# cyclone4.net
KiCad netlist of a schematic drawn in Altium Designer
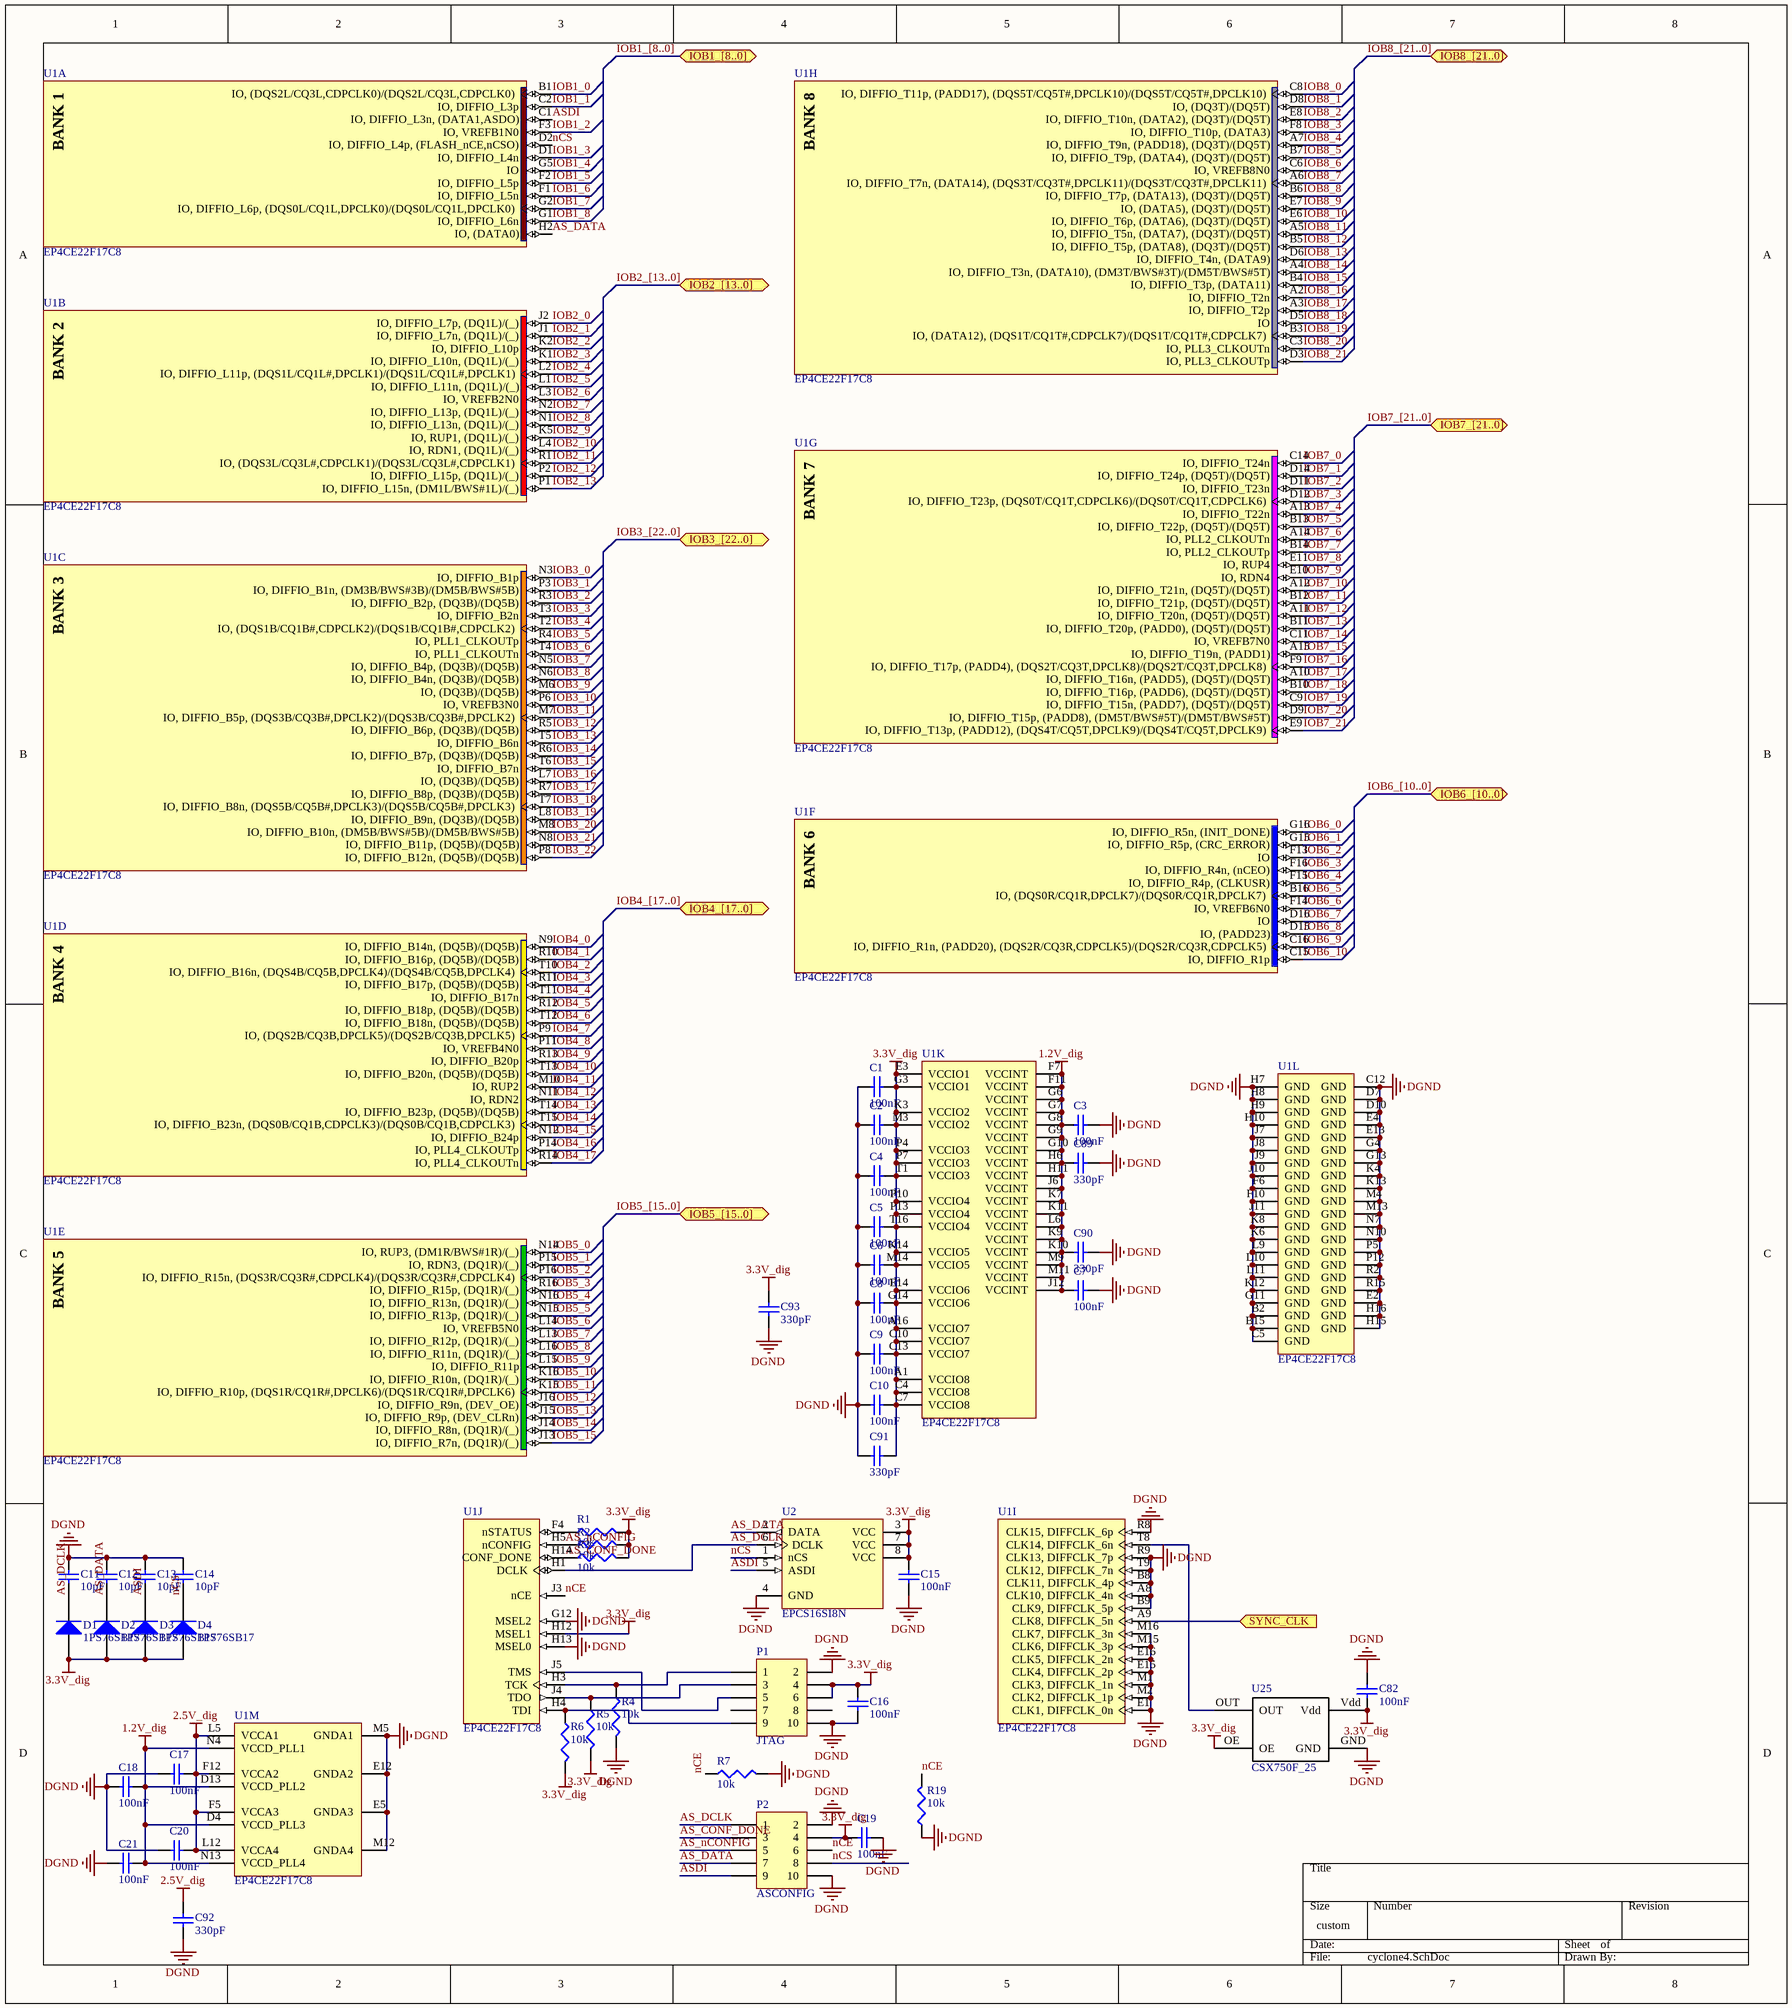
[diagram p0: cyclone4.SchDoc]

(export (version "E")
  (design (tool "Eeschema 10.0.6"))
  (components
    (comp (ref "C1")
      (value "100nF")
      (footprint "CAPC2012L")
      (description "Capacitor (Semiconductor SIM Model)")
      (fields (field (name "Comment") "Cap Semi"))
      (libsource (lib "Miscellaneous Devices") (part "Cap Semi"))
    )
    (comp (ref "C2")
      (value "100nF")
      (footprint "CAPC2012L")
      (description "Capacitor (Semiconductor SIM Model)")
      (fields (field (name "Comment") "Cap Semi"))
      (libsource (lib "Miscellaneous Devices") (part "Cap Semi"))
    )
    (comp (ref "C3")
      (value "100nF")
      (footprint "CAPC2012L")
      (description "Capacitor (Semiconductor SIM Model)")
      (fields (field (name "Comment") "Cap Semi"))
      (libsource (lib "Miscellaneous Devices") (part "Cap Semi"))
    )
    (comp (ref "C4")
      (value "100nF")
      (footprint "CAPC2012L")
      (description "Capacitor (Semiconductor SIM Model)")
      (fields (field (name "Comment") "Cap Semi"))
      (libsource (lib "Miscellaneous Devices") (part "Cap Semi"))
    )
    (comp (ref "C5")
      (value "100nF")
      (footprint "CAPC2012L")
      (description "Capacitor (Semiconductor SIM Model)")
      (fields (field (name "Comment") "Cap Semi"))
      (libsource (lib "Miscellaneous Devices") (part "Cap Semi"))
    )
    (comp (ref "C6")
      (value "100nF")
      (footprint "CAPC2012L")
      (description "Capacitor (Semiconductor SIM Model)")
      (fields (field (name "Comment") "Cap Semi"))
      (libsource (lib "Miscellaneous Devices") (part "Cap Semi"))
    )
    (comp (ref "C7")
      (value "100nF")
      (footprint "CAPC2012L")
      (description "Capacitor (Semiconductor SIM Model)")
      (fields (field (name "Comment") "Cap Semi"))
      (libsource (lib "Miscellaneous Devices") (part "Cap Semi"))
    )
    (comp (ref "C8")
      (value "100nF")
      (footprint "CAPC2012L")
      (description "Capacitor (Semiconductor SIM Model)")
      (fields (field (name "Comment") "Cap Semi"))
      (libsource (lib "Miscellaneous Devices") (part "Cap Semi"))
    )
    (comp (ref "C9")
      (value "100nF")
      (footprint "CAPC2012L")
      (description "Capacitor (Semiconductor SIM Model)")
      (fields (field (name "Comment") "Cap Semi"))
      (libsource (lib "Miscellaneous Devices") (part "Cap Semi"))
    )
    (comp (ref "C10")
      (value "100nF")
      (footprint "CAPC2012L")
      (description "Capacitor (Semiconductor SIM Model)")
      (fields (field (name "Comment") "Cap Semi"))
      (libsource (lib "Miscellaneous Devices") (part "Cap Semi"))
    )
    (comp (ref "C11")
      (value "10pF")
      (footprint "CAPC2012L")
      (description "Capacitor (Semiconductor SIM Model)")
      (fields (field (name "Comment") "Cap Semi"))
      (libsource (lib "Miscellaneous Devices") (part "Cap Semi"))
    )
    (comp (ref "C12")
      (value "10pF")
      (footprint "CAPC2012L")
      (description "Capacitor (Semiconductor SIM Model)")
      (fields (field (name "Comment") "Cap Semi"))
      (libsource (lib "Miscellaneous Devices") (part "Cap Semi"))
    )
    (comp (ref "C13")
      (value "10pF")
      (footprint "CAPC2012L")
      (description "Capacitor (Semiconductor SIM Model)")
      (fields (field (name "Comment") "Cap Semi"))
      (libsource (lib "Miscellaneous Devices") (part "Cap Semi"))
    )
    (comp (ref "C14")
      (value "10pF")
      (footprint "CAPC2012L")
      (description "Capacitor (Semiconductor SIM Model)")
      (fields (field (name "Comment") "Cap Semi"))
      (libsource (lib "Miscellaneous Devices") (part "Cap Semi"))
    )
    (comp (ref "C15")
      (value "100nF")
      (footprint "CAPC2012L")
      (description "Capacitor (Semiconductor SIM Model)")
      (fields (field (name "Comment") "Cap Semi"))
      (libsource (lib "Miscellaneous Devices") (part "Cap Semi"))
    )
    (comp (ref "C16")
      (value "100nF")
      (footprint "CAPC2012L")
      (description "Capacitor (Semiconductor SIM Model)")
      (fields (field (name "Comment") "Cap Semi"))
      (libsource (lib "Miscellaneous Devices") (part "Cap Semi"))
    )
    (comp (ref "C17")
      (value "100nF")
      (footprint "CAPC2012L")
      (description "Capacitor (Semiconductor SIM Model)")
      (fields (field (name "Comment") "Cap Semi"))
      (libsource (lib "Miscellaneous Devices") (part "Cap Semi"))
    )
    (comp (ref "C18")
      (value "100nF")
      (footprint "CAPC2012L")
      (description "Capacitor (Semiconductor SIM Model)")
      (fields (field (name "Comment") "Cap Semi"))
      (libsource (lib "Miscellaneous Devices") (part "Cap Semi"))
    )
    (comp (ref "C19")
      (value "100nF")
      (footprint "CAPC2012L")
      (description "Capacitor (Semiconductor SIM Model)")
      (fields (field (name "Comment") "Cap Semi"))
      (libsource (lib "Miscellaneous Devices") (part "Cap Semi"))
    )
    (comp (ref "C20")
      (value "100nF")
      (footprint "CAPC2012L")
      (description "Capacitor (Semiconductor SIM Model)")
      (fields (field (name "Comment") "Cap Semi"))
      (libsource (lib "Miscellaneous Devices") (part "Cap Semi"))
    )
    (comp (ref "C21")
      (value "100nF")
      (footprint "CAPC2012L")
      (description "Capacitor (Semiconductor SIM Model)")
      (fields (field (name "Comment") "Cap Semi"))
      (libsource (lib "Miscellaneous Devices") (part "Cap Semi"))
    )
    (comp (ref "C82")
      (value "100nF")
      (footprint "CAPC2012L")
      (description "Capacitor (Semiconductor SIM Model)")
      (fields (field (name "Comment") "Cap Semi"))
      (libsource (lib "Miscellaneous Devices") (part "Cap Semi"))
    )
    (comp (ref "C89")
      (value "330pF")
      (footprint "CAPC2012L")
      (description "Capacitor (Semiconductor SIM Model)")
      (fields (field (name "Comment") "Cap Semi"))
      (libsource (lib "Miscellaneous Devices") (part "Cap Semi"))
    )
    (comp (ref "C90")
      (value "330pF")
      (footprint "CAPC2012L")
      (description "Capacitor (Semiconductor SIM Model)")
      (fields (field (name "Comment") "Cap Semi"))
      (libsource (lib "Miscellaneous Devices") (part "Cap Semi"))
    )
    (comp (ref "C91")
      (value "330pF")
      (footprint "CAPC2012L")
      (description "Capacitor (Semiconductor SIM Model)")
      (fields (field (name "Comment") "Cap Semi"))
      (libsource (lib "Miscellaneous Devices") (part "Cap Semi"))
    )
    (comp (ref "C92")
      (value "330pF")
      (footprint "CAPC2012L")
      (description "Capacitor (Semiconductor SIM Model)")
      (fields (field (name "Comment") "Cap Semi"))
      (libsource (lib "Miscellaneous Devices") (part "Cap Semi"))
    )
    (comp (ref "C93")
      (value "330pF")
      (footprint "CAPC2012L")
      (description "Capacitor (Semiconductor SIM Model)")
      (fields (field (name "Comment") "Cap Semi"))
      (libsource (lib "Miscellaneous Devices") (part "Cap Semi"))
    )
    (comp (ref "D1")
      (value "1PS76SB17")
      (footprint "SOD323")
      (description "Default Diode")
      (libsource (lib "Miscellaneous Devices") (part "Diode"))
    )
    (comp (ref "D2")
      (value "1PS76SB17")
      (footprint "SOD323")
      (description "Default Diode")
      (libsource (lib "Miscellaneous Devices") (part "Diode"))
    )
    (comp (ref "D3")
      (value "1PS76SB17")
      (footprint "SOD323")
      (description "Default Diode")
      (libsource (lib "Miscellaneous Devices") (part "Diode"))
    )
    (comp (ref "D4")
      (value "1PS76SB17")
      (footprint "SOD323")
      (description "Default Diode")
      (libsource (lib "Miscellaneous Devices") (part "Diode"))
    )
    (comp (ref "P1")
      (value "JTAG")
      (footprint "HDR2X5")
      (description "Header, 5-Pin, Dual row")
      (libsource (lib "Miscellaneous Connectors") (part "Header 5X2"))
    )
    (comp (ref "P2")
      (value "ASCONFIG")
      (footprint "HDR2X5")
      (description "Header, 5-Pin, Dual row")
      (libsource (lib "Miscellaneous Connectors") (part "Header 5X2"))
    )
    (comp (ref "R1")
      (value "10k")
      (footprint "RESC3216L")
      (description "Resistor")
      (libsource (lib "Miscellaneous Devices") (part "Res3"))
    )
    (comp (ref "R2")
      (value "10k")
      (footprint "RESC3216L")
      (description "Resistor")
      (libsource (lib "Miscellaneous Devices") (part "Res3"))
    )
    (comp (ref "R3")
      (value "10k")
      (footprint "RESC3216L")
      (description "Resistor")
      (libsource (lib "Miscellaneous Devices") (part "Res3"))
    )
    (comp (ref "R4")
      (value "10k")
      (footprint "RESC3216L")
      (description "Resistor")
      (libsource (lib "Miscellaneous Devices") (part "Res3"))
    )
    (comp (ref "R5")
      (value "10k")
      (footprint "RESC3216L")
      (description "Resistor")
      (libsource (lib "Miscellaneous Devices") (part "Res3"))
    )
    (comp (ref "R6")
      (value "10k")
      (footprint "RESC3216L")
      (description "Resistor")
      (libsource (lib "Miscellaneous Devices") (part "Res3"))
    )
    (comp (ref "R7")
      (value "10k")
      (footprint "RESC3216L")
      (description "Resistor")
      (libsource (lib "Miscellaneous Devices") (part "Res3"))
    )
    (comp (ref "R19")
      (value "10k")
      (footprint "RESC3216L")
      (description "Resistor")
      (libsource (lib "Miscellaneous Devices") (part "Res3"))
    )
    (comp (ref "U1")
      (value "EP4CE22F17C8")
      (footprint "FBGA256")
      (libsource (lib "Altera Cyclone IV E") (part "EP4CE22F17C8"))
    )
    (comp (ref "U2")
      (value "EPCS16SI8N")
      (footprint "SOIC8_L")
      (libsource (lib "Altera EPCS Configuration Device") (part "EPCS4SI8N"))
    )
    (comp (ref "U25")
      (value "CSX750F_25")
      (footprint "CSX750F")
      (description "Clock Oscillator")
      (libsource (lib "HH_chips") (part "CSX750F"))
    )
  )
  (nets
    (net (code "1") (name "/ASDI") (class "Default")
      (node (ref "C13") (pin "1") (pinfunction "1_1") (pintype "passive"))
      (node (ref "D3") (pin "2") (pinfunction "K_2") (pintype "passive"))
      (node (ref "P2") (pin "9") (pinfunction "9_9") (pintype "passive"))
      (node (ref "U1") (pin "C1") (pinfunction "IO,_DIFFIO_L3n,_(DATA1,ASDO)_C1") (pintype "bidirectional"))
      (node (ref "U2") (pin "5") (pinfunction "ASDI_5") (pintype "input"))
    )
    (net (code "2") (name "/AS_CONF_DONE") (class "Default")
      (node (ref "P2") (pin "3") (pinfunction "3_3") (pintype "passive"))
      (node (ref "R3") (pin "1") (pinfunction "1_1") (pintype "passive"))
      (node (ref "U1") (pin "H14") (pinfunction "CONF_DONE_H14") (pintype "bidirectional"))
    )
    (net (code "3") (name "/AS_DATA") (class "Default")
      (node (ref "C12") (pin "1") (pinfunction "1_1") (pintype "passive"))
      (node (ref "D2") (pin "2") (pinfunction "K_2") (pintype "passive"))
      (node (ref "P2") (pin "7") (pinfunction "7_7") (pintype "passive"))
      (node (ref "U1") (pin "H2") (pinfunction "IO,_(DATA0)_H2") (pintype "bidirectional"))
      (node (ref "U2") (pin "2") (pinfunction "DATA_2") (pintype "output"))
    )
    (net (code "4") (name "/AS_DCLK") (class "Default")
      (node (ref "C11") (pin "1") (pinfunction "1_1") (pintype "passive"))
      (node (ref "D1") (pin "2") (pinfunction "K_2") (pintype "passive"))
      (node (ref "P2") (pin "1") (pinfunction "1_1") (pintype "passive"))
      (node (ref "U1") (pin "H1") (pinfunction "DCLK_H1") (pintype "bidirectional"))
      (node (ref "U2") (pin "6") (pinfunction "DCLK_6") (pintype "input"))
    )
    (net (code "5") (name "/AS_nCONFIG") (class "Default")
      (node (ref "P2") (pin "5") (pinfunction "5_5") (pintype "passive"))
      (node (ref "R2") (pin "1") (pinfunction "1_1") (pintype "passive"))
      (node (ref "U1") (pin "H5") (pinfunction "nCONFIG_H5") (pintype "input"))
    )
    (net (code "6") (name "/IOB1_0") (class "Default")
      (node (ref "U1") (pin "B1") (pinfunction "IO,_(DQS2L/CQ3L,CDPCLK0)/(DQS2L/CQ3L,CDPCLK0)_B1") (pintype "bidirectional"))
    )
    (net (code "7") (name "/IOB1_1") (class "Default")
      (node (ref "U1") (pin "C2") (pinfunction "IO,_DIFFIO_L3p_C2") (pintype "bidirectional"))
    )
    (net (code "8") (name "/IOB1_2") (class "Default")
      (node (ref "U1") (pin "F3") (pinfunction "IO,_VREFB1N0_F3") (pintype "bidirectional"))
    )
    (net (code "9") (name "/IOB1_3") (class "Default")
      (node (ref "U1") (pin "D1") (pinfunction "IO,_DIFFIO_L4n_D1") (pintype "bidirectional"))
    )
    (net (code "10") (name "/IOB1_4") (class "Default")
      (node (ref "U1") (pin "G5") (pinfunction "IO_G5") (pintype "bidirectional"))
    )
    (net (code "11") (name "/IOB1_5") (class "Default")
      (node (ref "U1") (pin "F2") (pinfunction "IO,_DIFFIO_L5p_F2") (pintype "bidirectional"))
    )
    (net (code "12") (name "/IOB1_6") (class "Default")
      (node (ref "U1") (pin "F1") (pinfunction "IO,_DIFFIO_L5n_F1") (pintype "bidirectional"))
    )
    (net (code "13") (name "/IOB1_7") (class "Default")
      (node (ref "U1") (pin "G2") (pinfunction "IO,_DIFFIO_L6p,_(DQS0L/CQ1L,DPCLK0)/(DQS0L/CQ1L,DPCLK0)_G2") (pintype "bidirectional"))
    )
    (net (code "14") (name "/IOB1_8") (class "Default")
      (node (ref "U1") (pin "G1") (pinfunction "IO,_DIFFIO_L6n_G1") (pintype "bidirectional"))
    )
    (net (code "16") (name "/IOB2_0") (class "Default")
      (node (ref "U1") (pin "J2") (pinfunction "IO,_DIFFIO_L7p,_(DQ1L)/(_)_J2") (pintype "bidirectional"))
    )
    (net (code "17") (name "/IOB2_1") (class "Default")
      (node (ref "U1") (pin "J1") (pinfunction "IO,_DIFFIO_L7n,_(DQ1L)/(_)_J1") (pintype "bidirectional"))
    )
    (net (code "18") (name "/IOB2_2") (class "Default")
      (node (ref "U1") (pin "K2") (pinfunction "IO,_DIFFIO_L10p_K2") (pintype "bidirectional"))
    )
    (net (code "19") (name "/IOB2_3") (class "Default")
      (node (ref "U1") (pin "K1") (pinfunction "IO,_DIFFIO_L10n,_(DQ1L)/(_)_K1") (pintype "bidirectional"))
    )
    (net (code "20") (name "/IOB2_4") (class "Default")
      (node (ref "U1") (pin "L2") (pinfunction "IO,_DIFFIO_L11p,_(DQS1L/CQ1L#,DPCLK1)/(DQS1L/CQ1L#,DPCLK1)_L2") (pintype "bidirectional"))
    )
    (net (code "21") (name "/IOB2_5") (class "Default")
      (node (ref "U1") (pin "L1") (pinfunction "IO,_DIFFIO_L11n,_(DQ1L)/(_)_L1") (pintype "bidirectional"))
    )
    (net (code "22") (name "/IOB2_6") (class "Default")
      (node (ref "U1") (pin "L3") (pinfunction "IO,_VREFB2N0_L3") (pintype "bidirectional"))
    )
    (net (code "23") (name "/IOB2_7") (class "Default")
      (node (ref "U1") (pin "N2") (pinfunction "IO,_DIFFIO_L13p,_(DQ1L)/(_)_N2") (pintype "bidirectional"))
    )
    (net (code "24") (name "/IOB2_8") (class "Default")
      (node (ref "U1") (pin "N1") (pinfunction "IO,_DIFFIO_L13n,_(DQ1L)/(_)_N1") (pintype "bidirectional"))
    )
    (net (code "25") (name "/IOB2_9") (class "Default")
      (node (ref "U1") (pin "K5") (pinfunction "IO,_RUP1,_(DQ1L)/(_)_K5") (pintype "bidirectional"))
    )
    (net (code "26") (name "/IOB2_10") (class "Default")
      (node (ref "U1") (pin "L4") (pinfunction "IO,_RDN1,_(DQ1L)/(_)_L4") (pintype "bidirectional"))
    )
    (net (code "27") (name "/IOB2_11") (class "Default")
      (node (ref "U1") (pin "R1") (pinfunction "IO,_(DQS3L/CQ3L#,CDPCLK1)/(DQS3L/CQ3L#,CDPCLK1)_R1") (pintype "bidirectional"))
    )
    (net (code "28") (name "/IOB2_12") (class "Default")
      (node (ref "U1") (pin "P2") (pinfunction "IO,_DIFFIO_L15p,_(DQ1L)/(_)_P2") (pintype "bidirectional"))
    )
    (net (code "29") (name "/IOB2_13") (class "Default")
      (node (ref "U1") (pin "P1") (pinfunction "IO,_DIFFIO_L15n,_(DM1L/BWS#1L)/(_)_P1") (pintype "bidirectional"))
    )
    (net (code "31") (name "/IOB3_0") (class "Default")
      (node (ref "U1") (pin "N3") (pinfunction "IO,_DIFFIO_B1p_N3") (pintype "bidirectional"))
    )
    (net (code "32") (name "/IOB3_1") (class "Default")
      (node (ref "U1") (pin "P3") (pinfunction "IO,_DIFFIO_B1n,_(DM3B/BWS#3B)/(DM5B/BWS#5B)_P3") (pintype "bidirectional"))
    )
    (net (code "33") (name "/IOB3_2") (class "Default")
      (node (ref "U1") (pin "R3") (pinfunction "IO,_DIFFIO_B2p,_(DQ3B)/(DQ5B)_R3") (pintype "bidirectional"))
    )
    (net (code "34") (name "/IOB3_3") (class "Default")
      (node (ref "U1") (pin "T3") (pinfunction "IO,_DIFFIO_B2n_T3") (pintype "bidirectional"))
    )
    (net (code "35") (name "/IOB3_4") (class "Default")
      (node (ref "U1") (pin "T2") (pinfunction "IO,_(DQS1B/CQ1B#,CDPCLK2)/(DQS1B/CQ1B#,CDPCLK2)_T2") (pintype "bidirectional"))
    )
    (net (code "36") (name "/IOB3_5") (class "Default")
      (node (ref "U1") (pin "R4") (pinfunction "IO,_PLL1_CLKOUTp_R4") (pintype "bidirectional"))
    )
    (net (code "37") (name "/IOB3_6") (class "Default")
      (node (ref "U1") (pin "T4") (pinfunction "IO,_PLL1_CLKOUTn_T4") (pintype "bidirectional"))
    )
    (net (code "38") (name "/IOB3_7") (class "Default")
      (node (ref "U1") (pin "N5") (pinfunction "IO,_DIFFIO_B4p,_(DQ3B)/(DQ5B)_N5") (pintype "bidirectional"))
    )
    (net (code "39") (name "/IOB3_8") (class "Default")
      (node (ref "U1") (pin "N6") (pinfunction "IO,_DIFFIO_B4n,_(DQ3B)/(DQ5B)_N6") (pintype "bidirectional"))
    )
    (net (code "40") (name "/IOB3_9") (class "Default")
      (node (ref "U1") (pin "M6") (pinfunction "IO,_(DQ3B)/(DQ5B)_M6") (pintype "bidirectional"))
    )
    (net (code "41") (name "/IOB3_10") (class "Default")
      (node (ref "U1") (pin "P6") (pinfunction "IO,_VREFB3N0_P6") (pintype "bidirectional"))
    )
    (net (code "42") (name "/IOB3_11") (class "Default")
      (node (ref "U1") (pin "M7") (pinfunction "IO,_DIFFIO_B5p,_(DQS3B/CQ3B#,DPCLK2)/(DQS3B/CQ3B#,DPCLK2)_M7") (pintype "bidirectional"))
    )
    (net (code "43") (name "/IOB3_12") (class "Default")
      (node (ref "U1") (pin "R5") (pinfunction "IO,_DIFFIO_B6p,_(DQ3B)/(DQ5B)_R5") (pintype "bidirectional"))
    )
    (net (code "44") (name "/IOB3_13") (class "Default")
      (node (ref "U1") (pin "T5") (pinfunction "IO,_DIFFIO_B6n_T5") (pintype "bidirectional"))
    )
    (net (code "45") (name "/IOB3_14") (class "Default")
      (node (ref "U1") (pin "R6") (pinfunction "IO,_DIFFIO_B7p,_(DQ3B)/(DQ5B)_R6") (pintype "bidirectional"))
    )
    (net (code "46") (name "/IOB3_15") (class "Default")
      (node (ref "U1") (pin "T6") (pinfunction "IO,_DIFFIO_B7n_T6") (pintype "bidirectional"))
    )
    (net (code "47") (name "/IOB3_16") (class "Default")
      (node (ref "U1") (pin "L7") (pinfunction "IO,_(DQ3B)/(DQ5B)_L7") (pintype "bidirectional"))
    )
    (net (code "48") (name "/IOB3_17") (class "Default")
      (node (ref "U1") (pin "R7") (pinfunction "IO,_DIFFIO_B8p,_(DQ3B)/(DQ5B)_R7") (pintype "bidirectional"))
    )
    (net (code "49") (name "/IOB3_18") (class "Default")
      (node (ref "U1") (pin "T7") (pinfunction "IO,_DIFFIO_B8n,_(DQS5B/CQ5B#,DPCLK3)/(DQS5B/CQ5B#,DPCLK3)_T7") (pintype "bidirectional"))
    )
    (net (code "50") (name "/IOB3_19") (class "Default")
      (node (ref "U1") (pin "L8") (pinfunction "IO,_DIFFIO_B9n,_(DQ3B)/(DQ5B)_L8") (pintype "bidirectional"))
    )
    (net (code "51") (name "/IOB3_20") (class "Default")
      (node (ref "U1") (pin "M8") (pinfunction "IO,_DIFFIO_B10n,_(DM5B/BWS#5B)/(DM5B/BWS#5B)_M8") (pintype "bidirectional"))
    )
    (net (code "52") (name "/IOB3_21") (class "Default")
      (node (ref "U1") (pin "N8") (pinfunction "IO,_DIFFIO_B11p,_(DQ5B)/(DQ5B)_N8") (pintype "bidirectional"))
    )
    (net (code "53") (name "/IOB3_22") (class "Default")
      (node (ref "U1") (pin "P8") (pinfunction "IO,_DIFFIO_B12n,_(DQ5B)/(DQ5B)_P8") (pintype "bidirectional"))
    )
    (net (code "55") (name "/IOB4_0") (class "Default")
      (node (ref "U1") (pin "N9") (pinfunction "IO,_DIFFIO_B14n,_(DQ5B)/(DQ5B)_N9") (pintype "bidirectional"))
    )
    (net (code "56") (name "/IOB4_1") (class "Default")
      (node (ref "U1") (pin "R10") (pinfunction "IO,_DIFFIO_B16p,_(DQ5B)/(DQ5B)_R10") (pintype "bidirectional"))
    )
    (net (code "57") (name "/IOB4_2") (class "Default")
      (node (ref "U1") (pin "T10") (pinfunction "IO,_DIFFIO_B16n,_(DQS4B/CQ5B,DPCLK4)/(DQS4B/CQ5B,DPCLK4)_T10") (pintype "bidirectional"))
    )
    (net (code "58") (name "/IOB4_3") (class "Default")
      (node (ref "U1") (pin "R11") (pinfunction "IO,_DIFFIO_B17p,_(DQ5B)/(DQ5B)_R11") (pintype "bidirectional"))
    )
    (net (code "59") (name "/IOB4_4") (class "Default")
      (node (ref "U1") (pin "T11") (pinfunction "IO,_DIFFIO_B17n_T11") (pintype "bidirectional"))
    )
    (net (code "60") (name "/IOB4_5") (class "Default")
      (node (ref "U1") (pin "R12") (pinfunction "IO,_DIFFIO_B18p,_(DQ5B)/(DQ5B)_R12") (pintype "bidirectional"))
    )
    (net (code "61") (name "/IOB4_6") (class "Default")
      (node (ref "U1") (pin "T12") (pinfunction "IO,_DIFFIO_B18n,_(DQ5B)/(DQ5B)_T12") (pintype "bidirectional"))
    )
    (net (code "62") (name "/IOB4_7") (class "Default")
      (node (ref "U1") (pin "P9") (pinfunction "IO,_(DQS2B/CQ3B,DPCLK5)/(DQS2B/CQ3B,DPCLK5)_P9") (pintype "bidirectional"))
    )
    (net (code "63") (name "/IOB4_8") (class "Default")
      (node (ref "U1") (pin "P11") (pinfunction "IO,_VREFB4N0_P11") (pintype "bidirectional"))
    )
    (net (code "64") (name "/IOB4_9") (class "Default")
      (node (ref "U1") (pin "R13") (pinfunction "IO,_DIFFIO_B20p_R13") (pintype "bidirectional"))
    )
    (net (code "65") (name "/IOB4_10") (class "Default")
      (node (ref "U1") (pin "T13") (pinfunction "IO,_DIFFIO_B20n,_(DQ5B)/(DQ5B)_T13") (pintype "bidirectional"))
    )
    (net (code "66") (name "/IOB4_11") (class "Default")
      (node (ref "U1") (pin "M10") (pinfunction "IO,_RUP2_M10") (pintype "bidirectional"))
    )
    (net (code "67") (name "/IOB4_12") (class "Default")
      (node (ref "U1") (pin "N11") (pinfunction "IO,_RDN2_N11") (pintype "bidirectional"))
    )
    (net (code "68") (name "/IOB4_13") (class "Default")
      (node (ref "U1") (pin "T14") (pinfunction "IO,_DIFFIO_B23p,_(DQ5B)/(DQ5B)_T14") (pintype "bidirectional"))
    )
    (net (code "69") (name "/IOB4_14") (class "Default")
      (node (ref "U1") (pin "T15") (pinfunction "IO,_DIFFIO_B23n,_(DQS0B/CQ1B,CDPCLK3)/(DQS0B/CQ1B,CDPCLK3)_T15") (pintype "bidirectional"))
    )
    (net (code "70") (name "/IOB4_15") (class "Default")
      (node (ref "U1") (pin "N12") (pinfunction "IO,_DIFFIO_B24p_N12") (pintype "bidirectional"))
    )
    (net (code "71") (name "/IOB4_16") (class "Default")
      (node (ref "U1") (pin "P14") (pinfunction "IO,_PLL4_CLKOUTp_P14") (pintype "bidirectional"))
    )
    (net (code "72") (name "/IOB4_17") (class "Default")
      (node (ref "U1") (pin "R14") (pinfunction "IO,_PLL4_CLKOUTn_R14") (pintype "bidirectional"))
    )
    (net (code "74") (name "/IOB5_0") (class "Default")
      (node (ref "U1") (pin "N14") (pinfunction "IO,_RUP3,_(DM1R/BWS#1R)/(_)_N14") (pintype "bidirectional"))
    )
    (net (code "75") (name "/IOB5_1") (class "Default")
      (node (ref "U1") (pin "P15") (pinfunction "IO,_RDN3,_(DQ1R)/(_)_P15") (pintype "bidirectional"))
    )
    (net (code "76") (name "/IOB5_2") (class "Default")
      (node (ref "U1") (pin "P16") (pinfunction "IO,_DIFFIO_R15n,_(DQS3R/CQ3R#,CDPCLK4)/(DQS3R/CQ3R#,CDPCLK4)_P16") (pintype "bidirectional"))
    )
    (net (code "77") (name "/IOB5_3") (class "Default")
      (node (ref "U1") (pin "R16") (pinfunction "IO,_DIFFIO_R15p,_(DQ1R)/(_)_R16") (pintype "bidirectional"))
    )
    (net (code "78") (name "/IOB5_4") (class "Default")
      (node (ref "U1") (pin "N16") (pinfunction "IO,_DIFFIO_R13n,_(DQ1R)/(_)_N16") (pintype "bidirectional"))
    )
    (net (code "79") (name "/IOB5_5") (class "Default")
      (node (ref "U1") (pin "N15") (pinfunction "IO,_DIFFIO_R13p,_(DQ1R)/(_)_N15") (pintype "bidirectional"))
    )
    (net (code "80") (name "/IOB5_6") (class "Default")
      (node (ref "U1") (pin "L14") (pinfunction "IO,_VREFB5N0_L14") (pintype "bidirectional"))
    )
    (net (code "81") (name "/IOB5_7") (class "Default")
      (node (ref "U1") (pin "L13") (pinfunction "IO,_DIFFIO_R12p,_(DQ1R)/(_)_L13") (pintype "bidirectional"))
    )
    (net (code "82") (name "/IOB5_8") (class "Default")
      (node (ref "U1") (pin "L16") (pinfunction "IO,_DIFFIO_R11n,_(DQ1R)/(_)_L16") (pintype "bidirectional"))
    )
    (net (code "83") (name "/IOB5_9") (class "Default")
      (node (ref "U1") (pin "L15") (pinfunction "IO,_DIFFIO_R11p_L15") (pintype "bidirectional"))
    )
    (net (code "84") (name "/IOB5_10") (class "Default")
      (node (ref "U1") (pin "K16") (pinfunction "IO,_DIFFIO_R10n,_(DQ1R)/(_)_K16") (pintype "bidirectional"))
    )
    (net (code "85") (name "/IOB5_11") (class "Default")
      (node (ref "U1") (pin "K15") (pinfunction "IO,_DIFFIO_R10p,_(DQS1R/CQ1R#,DPCLK6)/(DQS1R/CQ1R#,DPCLK6)_K15") (pintype "bidirectional"))
    )
    (net (code "86") (name "/IOB5_12") (class "Default")
      (node (ref "U1") (pin "J16") (pinfunction "IO,_DIFFIO_R9n,_(DEV_OE)_J16") (pintype "bidirectional"))
    )
    (net (code "87") (name "/IOB5_13") (class "Default")
      (node (ref "U1") (pin "J15") (pinfunction "IO,_DIFFIO_R9p,_(DEV_CLRn)_J15") (pintype "bidirectional"))
    )
    (net (code "88") (name "/IOB5_14") (class "Default")
      (node (ref "U1") (pin "J14") (pinfunction "IO,_DIFFIO_R8n,_(DQ1R)/(_)_J14") (pintype "bidirectional"))
    )
    (net (code "89") (name "/IOB5_15") (class "Default")
      (node (ref "U1") (pin "J13") (pinfunction "IO,_DIFFIO_R7n,_(DQ1R)/(_)_J13") (pintype "bidirectional"))
    )
    (net (code "91") (name "/IOB6_0") (class "Default")
      (node (ref "U1") (pin "G16") (pinfunction "IO,_DIFFIO_R5n,_(INIT_DONE)_G16") (pintype "bidirectional"))
    )
    (net (code "92") (name "/IOB6_1") (class "Default")
      (node (ref "U1") (pin "G15") (pinfunction "IO,_DIFFIO_R5p,_(CRC_ERROR)_G15") (pintype "bidirectional"))
    )
    (net (code "93") (name "/IOB6_2") (class "Default")
      (node (ref "U1") (pin "F13") (pinfunction "IO_F13") (pintype "bidirectional"))
    )
    (net (code "94") (name "/IOB6_3") (class "Default")
      (node (ref "U1") (pin "F16") (pinfunction "IO,_DIFFIO_R4n,_(nCEO)_F16") (pintype "bidirectional"))
    )
    (net (code "95") (name "/IOB6_4") (class "Default")
      (node (ref "U1") (pin "F15") (pinfunction "IO,_DIFFIO_R4p,_(CLKUSR)_F15") (pintype "bidirectional"))
    )
    (net (code "96") (name "/IOB6_5") (class "Default")
      (node (ref "U1") (pin "B16") (pinfunction "IO,_(DQS0R/CQ1R,DPCLK7)/(DQS0R/CQ1R,DPCLK7)_B16") (pintype "bidirectional"))
    )
    (net (code "97") (name "/IOB6_6") (class "Default")
      (node (ref "U1") (pin "F14") (pinfunction "IO,_VREFB6N0_F14") (pintype "bidirectional"))
    )
    (net (code "98") (name "/IOB6_7") (class "Default")
      (node (ref "U1") (pin "D16") (pinfunction "IO_D16") (pintype "bidirectional"))
    )
    (net (code "99") (name "/IOB6_8") (class "Default")
      (node (ref "U1") (pin "D15") (pinfunction "IO,_(PADD23)_D15") (pintype "bidirectional"))
    )
    (net (code "100") (name "/IOB6_9") (class "Default")
      (node (ref "U1") (pin "C16") (pinfunction "IO,_DIFFIO_R1n,_(PADD20),_(DQS2R/CQ3R,CDPCLK5)/(DQS2R/CQ3R,CDPCLK5)_C16") (pintype "bidirectional"))
    )
    (net (code "101") (name "/IOB6_10") (class "Default")
      (node (ref "U1") (pin "C15") (pinfunction "IO,_DIFFIO_R1p_C15") (pintype "bidirectional"))
    )
    (net (code "103") (name "/IOB7_0") (class "Default")
      (node (ref "U1") (pin "C14") (pinfunction "IO,_DIFFIO_T24n_C14") (pintype "bidirectional"))
    )
    (net (code "104") (name "/IOB7_1") (class "Default")
      (node (ref "U1") (pin "D14") (pinfunction "IO,_DIFFIO_T24p,_(DQ5T)/(DQ5T)_D14") (pintype "bidirectional"))
    )
    (net (code "105") (name "/IOB7_2") (class "Default")
      (node (ref "U1") (pin "D11") (pinfunction "IO,_DIFFIO_T23n_D11") (pintype "bidirectional"))
    )
    (net (code "106") (name "/IOB7_3") (class "Default")
      (node (ref "U1") (pin "D12") (pinfunction "IO,_DIFFIO_T23p,_(DQS0T/CQ1T,CDPCLK6)/(DQS0T/CQ1T,CDPCLK6)_D12") (pintype "bidirectional"))
    )
    (net (code "107") (name "/IOB7_4") (class "Default")
      (node (ref "U1") (pin "A13") (pinfunction "IO,_DIFFIO_T22n_A13") (pintype "bidirectional"))
    )
    (net (code "108") (name "/IOB7_5") (class "Default")
      (node (ref "U1") (pin "B13") (pinfunction "IO,_DIFFIO_T22p,_(DQ5T)/(DQ5T)_B13") (pintype "bidirectional"))
    )
    (net (code "109") (name "/IOB7_6") (class "Default")
      (node (ref "U1") (pin "A14") (pinfunction "IO,_PLL2_CLKOUTn_A14") (pintype "bidirectional"))
    )
    (net (code "110") (name "/IOB7_7") (class "Default")
      (node (ref "U1") (pin "B14") (pinfunction "IO,_PLL2_CLKOUTp_B14") (pintype "bidirectional"))
    )
    (net (code "111") (name "/IOB7_8") (class "Default")
      (node (ref "U1") (pin "E11") (pinfunction "IO,_RUP4_E11") (pintype "bidirectional"))
    )
    (net (code "112") (name "/IOB7_9") (class "Default")
      (node (ref "U1") (pin "E10") (pinfunction "IO,_RDN4_E10") (pintype "bidirectional"))
    )
    (net (code "113") (name "/IOB7_10") (class "Default")
      (node (ref "U1") (pin "A12") (pinfunction "IO,_DIFFIO_T21n,_(DQ5T)/(DQ5T)_A12") (pintype "bidirectional"))
    )
    (net (code "114") (name "/IOB7_11") (class "Default")
      (node (ref "U1") (pin "B12") (pinfunction "IO,_DIFFIO_T21p,_(DQ5T)/(DQ5T)_B12") (pintype "bidirectional"))
    )
    (net (code "115") (name "/IOB7_12") (class "Default")
      (node (ref "U1") (pin "A11") (pinfunction "IO,_DIFFIO_T20n,_(DQ5T)/(DQ5T)_A11") (pintype "bidirectional"))
    )
    (net (code "116") (name "/IOB7_13") (class "Default")
      (node (ref "U1") (pin "B11") (pinfunction "IO,_DIFFIO_T20p,_(PADD0),_(DQ5T)/(DQ5T)_B11") (pintype "bidirectional"))
    )
    (net (code "117") (name "/IOB7_14") (class "Default")
      (node (ref "U1") (pin "C11") (pinfunction "IO,_VREFB7N0_C11") (pintype "bidirectional"))
    )
    (net (code "118") (name "/IOB7_15") (class "Default")
      (node (ref "U1") (pin "A15") (pinfunction "IO,_DIFFIO_T19n,_(PADD1)_A15") (pintype "bidirectional"))
    )
    (net (code "119") (name "/IOB7_16") (class "Default")
      (node (ref "U1") (pin "F9") (pinfunction "IO,_DIFFIO_T17p,_(PADD4),_(DQS2T/CQ3T,DPCLK8)/(DQS2T/CQ3T,DPCLK8)_F9") (pintype "bidirectional"))
    )
    (net (code "120") (name "/IOB7_17") (class "Default")
      (node (ref "U1") (pin "A10") (pinfunction "IO,_DIFFIO_T16n,_(PADD5),_(DQ5T)/(DQ5T)_A10") (pintype "bidirectional"))
    )
    (net (code "121") (name "/IOB7_18") (class "Default")
      (node (ref "U1") (pin "B10") (pinfunction "IO,_DIFFIO_T16p,_(PADD6),_(DQ5T)/(DQ5T)_B10") (pintype "bidirectional"))
    )
    (net (code "122") (name "/IOB7_19") (class "Default")
      (node (ref "U1") (pin "C9") (pinfunction "IO,_DIFFIO_T15n,_(PADD7),_(DQ5T)/(DQ5T)_C9") (pintype "bidirectional"))
    )
    (net (code "123") (name "/IOB7_20") (class "Default")
      (node (ref "U1") (pin "D9") (pinfunction "IO,_DIFFIO_T15p,_(PADD8),_(DM5T/BWS#5T)/(DM5T/BWS#5T)_D9") (pintype "bidirectional"))
    )
    (net (code "124") (name "/IOB7_21") (class "Default")
      (node (ref "U1") (pin "E9") (pinfunction "IO,_DIFFIO_T13p,_(PADD12),_(DQS4T/CQ5T,DPCLK9)/(DQS4T/CQ5T,DPCLK9)_E9") (pintype "bidirectional"))
    )
    (net (code "126") (name "/IOB8_0") (class "Default")
      (node (ref "U1") (pin "C8") (pinfunction "IO,_DIFFIO_T11p,_(PADD17),_(DQS5T/CQ5T#,DPCLK10)/(DQS5T/CQ5T#,DPCLK10)_C8") (pintype "bidirectional"))
    )
    (net (code "127") (name "/IOB8_1") (class "Default")
      (node (ref "U1") (pin "D8") (pinfunction "IO,_(DQ3T)/(DQ5T)_D8") (pintype "bidirectional"))
    )
    (net (code "128") (name "/IOB8_2") (class "Default")
      (node (ref "U1") (pin "E8") (pinfunction "IO,_DIFFIO_T10n,_(DATA2),_(DQ3T)/(DQ5T)_E8") (pintype "bidirectional"))
    )
    (net (code "129") (name "/IOB8_3") (class "Default")
      (node (ref "U1") (pin "F8") (pinfunction "IO,_DIFFIO_T10p,_(DATA3)_F8") (pintype "bidirectional"))
    )
    (net (code "130") (name "/IOB8_4") (class "Default")
      (node (ref "U1") (pin "A7") (pinfunction "IO,_DIFFIO_T9n,_(PADD18),_(DQ3T)/(DQ5T)_A7") (pintype "bidirectional"))
    )
    (net (code "131") (name "/IOB8_5") (class "Default")
      (node (ref "U1") (pin "B7") (pinfunction "IO,_DIFFIO_T9p,_(DATA4),_(DQ3T)/(DQ5T)_B7") (pintype "bidirectional"))
    )
    (net (code "132") (name "/IOB8_6") (class "Default")
      (node (ref "U1") (pin "C6") (pinfunction "IO,_VREFB8N0_C6") (pintype "bidirectional"))
    )
    (net (code "133") (name "/IOB8_7") (class "Default")
      (node (ref "U1") (pin "A6") (pinfunction "IO,_DIFFIO_T7n,_(DATA14),_(DQS3T/CQ3T#,DPCLK11)/(DQS3T/CQ3T#,DPCLK11)_A6") (pintype "bidirectional"))
    )
    (net (code "134") (name "/IOB8_8") (class "Default")
      (node (ref "U1") (pin "B6") (pinfunction "IO,_DIFFIO_T7p,_(DATA13),_(DQ3T)/(DQ5T)_B6") (pintype "bidirectional"))
    )
    (net (code "135") (name "/IOB8_9") (class "Default")
      (node (ref "U1") (pin "E7") (pinfunction "IO,_(DATA5),_(DQ3T)/(DQ5T)_E7") (pintype "bidirectional"))
    )
    (net (code "136") (name "/IOB8_10") (class "Default")
      (node (ref "U1") (pin "E6") (pinfunction "IO,_DIFFIO_T6p,_(DATA6),_(DQ3T)/(DQ5T)_E6") (pintype "bidirectional"))
    )
    (net (code "137") (name "/IOB8_11") (class "Default")
      (node (ref "U1") (pin "A5") (pinfunction "IO,_DIFFIO_T5n,_(DATA7),_(DQ3T)/(DQ5T)_A5") (pintype "bidirectional"))
    )
    (net (code "138") (name "/IOB8_12") (class "Default")
      (node (ref "U1") (pin "B5") (pinfunction "IO,_DIFFIO_T5p,_(DATA8),_(DQ3T)/(DQ5T)_B5") (pintype "bidirectional"))
    )
    (net (code "139") (name "/IOB8_13") (class "Default")
      (node (ref "U1") (pin "D6") (pinfunction "IO,_DIFFIO_T4n,_(DATA9)_D6") (pintype "bidirectional"))
    )
    (net (code "140") (name "/IOB8_14") (class "Default")
      (node (ref "U1") (pin "A4") (pinfunction "IO,_DIFFIO_T3n,_(DATA10),_(DM3T/BWS#3T)/(DM5T/BWS#5T)_A4") (pintype "bidirectional"))
    )
    (net (code "141") (name "/IOB8_15") (class "Default")
      (node (ref "U1") (pin "B4") (pinfunction "IO,_DIFFIO_T3p,_(DATA11)_B4") (pintype "bidirectional"))
    )
    (net (code "142") (name "/IOB8_16") (class "Default")
      (node (ref "U1") (pin "A2") (pinfunction "IO,_DIFFIO_T2n_A2") (pintype "bidirectional"))
    )
    (net (code "143") (name "/IOB8_17") (class "Default")
      (node (ref "U1") (pin "A3") (pinfunction "IO,_DIFFIO_T2p_A3") (pintype "bidirectional"))
    )
    (net (code "144") (name "/IOB8_18") (class "Default")
      (node (ref "U1") (pin "D5") (pinfunction "IO_D5") (pintype "bidirectional"))
    )
    (net (code "145") (name "/IOB8_19") (class "Default")
      (node (ref "U1") (pin "B3") (pinfunction "IO,_(DATA12),_(DQS1T/CQ1T#,CDPCLK7)/(DQS1T/CQ1T#,CDPCLK7)_B3") (pintype "bidirectional"))
    )
    (net (code "146") (name "/IOB8_20") (class "Default")
      (node (ref "U1") (pin "C3") (pinfunction "IO,_PLL3_CLKOUTn_C3") (pintype "bidirectional"))
    )
    (net (code "147") (name "/IOB8_21") (class "Default")
      (node (ref "U1") (pin "D3") (pinfunction "IO,_PLL3_CLKOUTp_D3") (pintype "bidirectional"))
    )
    (net (code "149") (name "/SYNC_CLK") (class "Default")
      (node (ref "U1") (pin "A9") (pinfunction "CLK8,_DIFFCLK_5n_A9") (pintype "input"))
    )
    (net (code "150") (name "/nCE") (class "Default")
      (node (ref "P2") (pin "6") (pinfunction "6_6") (pintype "passive"))
      (node (ref "R19") (pin "2") (pinfunction "2_2") (pintype "passive"))
      (node (ref "R7") (pin "1") (pinfunction "1_1") (pintype "passive"))
      (node (ref "U1") (pin "J3") (pinfunction "nCE_J3") (pintype "input"))
    )
    (net (code "151") (name "/nCS") (class "Default")
      (node (ref "C14") (pin "1") (pinfunction "1_1") (pintype "passive"))
      (node (ref "D4") (pin "2") (pinfunction "K_2") (pintype "passive"))
      (node (ref "P2") (pin "8") (pinfunction "8_8") (pintype "passive"))
      (node (ref "U1") (pin "D2") (pinfunction "IO,_DIFFIO_L4p,_(FLASH_nCE,nCSO)_D2") (pintype "bidirectional"))
      (node (ref "U2") (pin "1") (pinfunction "nCS_1") (pintype "input"))
    )
    (net (code "152") (name "1.2V_dig") (class "Default")
      (node (ref "C18") (pin "2") (pinfunction "2_2") (pintype "passive"))
      (node (ref "C21") (pin "2") (pinfunction "2_2") (pintype "passive"))
      (node (ref "C3") (pin "1") (pinfunction "1_1") (pintype "passive"))
      (node (ref "C7") (pin "1") (pinfunction "1_1") (pintype "passive"))
      (node (ref "C89") (pin "1") (pinfunction "1_1") (pintype "passive"))
      (node (ref "C90") (pin "1") (pinfunction "1_1") (pintype "passive"))
      (node (ref "U1") (pin "D13") (pinfunction "VCCD_PLL2_D13") (pintype "power_in"))
      (node (ref "U1") (pin "D4") (pinfunction "VCCD_PLL3_D4") (pintype "power_in"))
      (node (ref "U1") (pin "F11") (pinfunction "VCCINT_F11") (pintype "power_in"))
      (node (ref "U1") (pin "F7") (pinfunction "VCCINT_F7") (pintype "power_in"))
      (node (ref "U1") (pin "G10") (pinfunction "VCCINT_G10") (pintype "power_in"))
      (node (ref "U1") (pin "G6") (pinfunction "VCCINT_G6") (pintype "power_in"))
      (node (ref "U1") (pin "G7") (pinfunction "VCCINT_G7") (pintype "power_in"))
      (node (ref "U1") (pin "G8") (pinfunction "VCCINT_G8") (pintype "power_in"))
      (node (ref "U1") (pin "G9") (pinfunction "VCCINT_G9") (pintype "power_in"))
      (node (ref "U1") (pin "H11") (pinfunction "VCCINT_H11") (pintype "power_in"))
      (node (ref "U1") (pin "H6") (pinfunction "VCCINT_H6") (pintype "power_in"))
      (node (ref "U1") (pin "J12") (pinfunction "VCCINT_J12") (pintype "power_in"))
      (node (ref "U1") (pin "J6") (pinfunction "VCCINT_J6") (pintype "power_in"))
      (node (ref "U1") (pin "K10") (pinfunction "VCCINT_K10") (pintype "power_in"))
      (node (ref "U1") (pin "K11") (pinfunction "VCCINT_K11") (pintype "power_in"))
      (node (ref "U1") (pin "K7") (pinfunction "VCCINT_K7") (pintype "power_in"))
      (node (ref "U1") (pin "K9") (pinfunction "VCCINT_K9") (pintype "power_in"))
      (node (ref "U1") (pin "L6") (pinfunction "VCCINT_L6") (pintype "power_in"))
      (node (ref "U1") (pin "M11") (pinfunction "VCCINT_M11") (pintype "power_in"))
      (node (ref "U1") (pin "M9") (pinfunction "VCCINT_M9") (pintype "power_in"))
      (node (ref "U1") (pin "N13") (pinfunction "VCCD_PLL4_N13") (pintype "power_in"))
      (node (ref "U1") (pin "N4") (pinfunction "VCCD_PLL1_N4") (pintype "power_in"))
    )
    (net (code "153") (name "2.5V_dig") (class "Default")
      (node (ref "C17") (pin "2") (pinfunction "2_2") (pintype "passive"))
      (node (ref "C20") (pin "1") (pinfunction "1_1") (pintype "passive"))
      (node (ref "C92") (pin "2") (pinfunction "2_2") (pintype "passive"))
      (node (ref "U1") (pin "F12") (pinfunction "VCCA2_F12") (pintype "power_in"))
      (node (ref "U1") (pin "F5") (pinfunction "VCCA3_F5") (pintype "power_in"))
      (node (ref "U1") (pin "L12") (pinfunction "VCCA4_L12") (pintype "power_in"))
      (node (ref "U1") (pin "L5") (pinfunction "VCCA1_L5") (pintype "power_in"))
    )
    (net (code "154") (name "3.3V_dig") (class "Default")
      (node (ref "C1") (pin "2") (pinfunction "2_2") (pintype "passive"))
      (node (ref "C10") (pin "2") (pinfunction "2_2") (pintype "passive"))
      (node (ref "C15") (pin "1") (pinfunction "1_1") (pintype "passive"))
      (node (ref "C16") (pin "1") (pinfunction "1_1") (pintype "passive"))
      (node (ref "C19") (pin "1") (pinfunction "1_1") (pintype "passive"))
      (node (ref "C2") (pin "2") (pinfunction "2_2") (pintype "passive"))
      (node (ref "C4") (pin "2") (pinfunction "2_2") (pintype "passive"))
      (node (ref "C5") (pin "2") (pinfunction "2_2") (pintype "passive"))
      (node (ref "C6") (pin "2") (pinfunction "2_2") (pintype "passive"))
      (node (ref "C8") (pin "2") (pinfunction "2_2") (pintype "passive"))
      (node (ref "C82") (pin "2") (pinfunction "2_2") (pintype "passive"))
      (node (ref "C9") (pin "2") (pinfunction "2_2") (pintype "passive"))
      (node (ref "C91") (pin "2") (pinfunction "2_2") (pintype "passive"))
      (node (ref "C93") (pin "2") (pinfunction "2_2") (pintype "passive"))
      (node (ref "D1") (pin "1") (pinfunction "A_1") (pintype "passive"))
      (node (ref "D2") (pin "1") (pinfunction "A_1") (pintype "passive"))
      (node (ref "D3") (pin "1") (pinfunction "A_1") (pintype "passive"))
      (node (ref "D4") (pin "1") (pinfunction "A_1") (pintype "passive"))
      (node (ref "P1") (pin "4") (pinfunction "4_4") (pintype "passive"))
      (node (ref "P1") (pin "6") (pinfunction "6_6") (pintype "passive"))
      (node (ref "P2") (pin "4") (pinfunction "4_4") (pintype "passive"))
      (node (ref "R1") (pin "2") (pinfunction "2_2") (pintype "passive"))
      (node (ref "R2") (pin "2") (pinfunction "2_2") (pintype "passive"))
      (node (ref "R3") (pin "2") (pinfunction "2_2") (pintype "passive"))
      (node (ref "R5") (pin "2") (pinfunction "2_2") (pintype "passive"))
      (node (ref "R6") (pin "2") (pinfunction "2_2") (pintype "passive"))
      (node (ref "U1") (pin "A1") (pinfunction "VCCIO8_A1") (pintype "power_in"))
      (node (ref "U1") (pin "A16") (pinfunction "VCCIO7_A16") (pintype "power_in"))
      (node (ref "U1") (pin "C10") (pinfunction "VCCIO7_C10") (pintype "power_in"))
      (node (ref "U1") (pin "C13") (pinfunction "VCCIO7_C13") (pintype "power_in"))
      (node (ref "U1") (pin "C4") (pinfunction "VCCIO8_C4") (pintype "power_in"))
      (node (ref "U1") (pin "C7") (pinfunction "VCCIO8_C7") (pintype "power_in"))
      (node (ref "U1") (pin "E14") (pinfunction "VCCIO6_E14") (pintype "power_in"))
      (node (ref "U1") (pin "E3") (pinfunction "VCCIO1_E3") (pintype "power_in"))
      (node (ref "U1") (pin "G14") (pinfunction "VCCIO6_G14") (pintype "power_in"))
      (node (ref "U1") (pin "G3") (pinfunction "VCCIO1_G3") (pintype "power_in"))
      (node (ref "U1") (pin "H12") (pinfunction "MSEL1_H12") (pintype "input"))
      (node (ref "U1") (pin "K14") (pinfunction "VCCIO5_K14") (pintype "power_in"))
      (node (ref "U1") (pin "K3") (pinfunction "VCCIO2_K3") (pintype "power_in"))
      (node (ref "U1") (pin "M14") (pinfunction "VCCIO5_M14") (pintype "power_in"))
      (node (ref "U1") (pin "M3") (pinfunction "VCCIO2_M3") (pintype "power_in"))
      (node (ref "U1") (pin "P10") (pinfunction "VCCIO4_P10") (pintype "power_in"))
      (node (ref "U1") (pin "P13") (pinfunction "VCCIO4_P13") (pintype "power_in"))
      (node (ref "U1") (pin "P4") (pinfunction "VCCIO3_P4") (pintype "power_in"))
      (node (ref "U1") (pin "P7") (pinfunction "VCCIO3_P7") (pintype "power_in"))
      (node (ref "U1") (pin "T1") (pinfunction "VCCIO3_T1") (pintype "power_in"))
      (node (ref "U1") (pin "T16") (pinfunction "VCCIO4_T16") (pintype "power_in"))
      (node (ref "U2") (pin "3") (pinfunction "VCC_3") (pintype "power_in"))
      (node (ref "U2") (pin "7") (pinfunction "VCC_7") (pintype "power_in"))
      (node (ref "U2") (pin "8") (pinfunction "VCC_8") (pintype "power_in"))
      (node (ref "U25") (pin "OE") (pinfunction "OE_OE") (pintype "passive"))
      (node (ref "U25") (pin "Vdd") (pinfunction "Vdd_Vdd") (pintype "passive"))
    )
    (net (code "155") (name "DGND") (class "Default")
      (node (ref "C1") (pin "1") (pinfunction "1_1") (pintype "passive"))
      (node (ref "C10") (pin "1") (pinfunction "1_1") (pintype "passive"))
      (node (ref "C11") (pin "2") (pinfunction "2_2") (pintype "passive"))
      (node (ref "C12") (pin "2") (pinfunction "2_2") (pintype "passive"))
      (node (ref "C13") (pin "2") (pinfunction "2_2") (pintype "passive"))
      (node (ref "C14") (pin "2") (pinfunction "2_2") (pintype "passive"))
      (node (ref "C15") (pin "2") (pinfunction "2_2") (pintype "passive"))
      (node (ref "C16") (pin "2") (pinfunction "2_2") (pintype "passive"))
      (node (ref "C17") (pin "1") (pinfunction "1_1") (pintype "passive"))
      (node (ref "C18") (pin "1") (pinfunction "1_1") (pintype "passive"))
      (node (ref "C19") (pin "2") (pinfunction "2_2") (pintype "passive"))
      (node (ref "C2") (pin "1") (pinfunction "1_1") (pintype "passive"))
      (node (ref "C20") (pin "2") (pinfunction "2_2") (pintype "passive"))
      (node (ref "C21") (pin "1") (pinfunction "1_1") (pintype "passive"))
      (node (ref "C3") (pin "2") (pinfunction "2_2") (pintype "passive"))
      (node (ref "C4") (pin "1") (pinfunction "1_1") (pintype "passive"))
      (node (ref "C5") (pin "1") (pinfunction "1_1") (pintype "passive"))
      (node (ref "C6") (pin "1") (pinfunction "1_1") (pintype "passive"))
      (node (ref "C7") (pin "2") (pinfunction "2_2") (pintype "passive"))
      (node (ref "C8") (pin "1") (pinfunction "1_1") (pintype "passive"))
      (node (ref "C82") (pin "1") (pinfunction "1_1") (pintype "passive"))
      (node (ref "C89") (pin "2") (pinfunction "2_2") (pintype "passive"))
      (node (ref "C9") (pin "1") (pinfunction "1_1") (pintype "passive"))
      (node (ref "C90") (pin "2") (pinfunction "2_2") (pintype "passive"))
      (node (ref "C91") (pin "1") (pinfunction "1_1") (pintype "passive"))
      (node (ref "C92") (pin "1") (pinfunction "1_1") (pintype "passive"))
      (node (ref "C93") (pin "1") (pinfunction "1_1") (pintype "passive"))
      (node (ref "P1") (pin "10") (pinfunction "10_10") (pintype "passive"))
      (node (ref "P1") (pin "2") (pinfunction "2_2") (pintype "passive"))
      (node (ref "P2") (pin "10") (pinfunction "10_10") (pintype "passive"))
      (node (ref "P2") (pin "2") (pinfunction "2_2") (pintype "passive"))
      (node (ref "R19") (pin "1") (pinfunction "1_1") (pintype "passive"))
      (node (ref "R4") (pin "2") (pinfunction "2_2") (pintype "passive"))
      (node (ref "R7") (pin "2") (pinfunction "2_2") (pintype "passive"))
      (node (ref "U1") (pin "A8") (pinfunction "CLK10,_DIFFCLK_4n_A8") (pintype "input"))
      (node (ref "U1") (pin "B15") (pinfunction "GND_B15") (pintype "power_in"))
      (node (ref "U1") (pin "B2") (pinfunction "GND_B2") (pintype "power_in"))
      (node (ref "U1") (pin "B8") (pinfunction "CLK11,_DIFFCLK_4p_B8") (pintype "input"))
      (node (ref "U1") (pin "B9") (pinfunction "CLK9,_DIFFCLK_5p_B9") (pintype "input"))
      (node (ref "U1") (pin "C12") (pinfunction "GND_C12") (pintype "power_in"))
      (node (ref "U1") (pin "C5") (pinfunction "GND_C5") (pintype "power_in"))
      (node (ref "U1") (pin "D10") (pinfunction "GND_D10") (pintype "power_in"))
      (node (ref "U1") (pin "D7") (pinfunction "GND_D7") (pintype "power_in"))
      (node (ref "U1") (pin "E1") (pinfunction "CLK1,_DIFFCLK_0n_E1") (pintype "input"))
      (node (ref "U1") (pin "E12") (pinfunction "GNDA2_E12") (pintype "power_in"))
      (node (ref "U1") (pin "E13") (pinfunction "GND_E13") (pintype "power_in"))
      (node (ref "U1") (pin "E15") (pinfunction "CLK4,_DIFFCLK_2p_E15") (pintype "input"))
      (node (ref "U1") (pin "E16") (pinfunction "CLK5,_DIFFCLK_2n_E16") (pintype "input"))
      (node (ref "U1") (pin "E2") (pinfunction "GND_E2") (pintype "power_in"))
      (node (ref "U1") (pin "E4") (pinfunction "GND_E4") (pintype "power_in"))
      (node (ref "U1") (pin "E5") (pinfunction "GNDA3_E5") (pintype "power_in"))
      (node (ref "U1") (pin "F10") (pinfunction "GND_F10") (pintype "power_in"))
      (node (ref "U1") (pin "F6") (pinfunction "GND_F6") (pintype "power_in"))
      (node (ref "U1") (pin "G11") (pinfunction "GND_G11") (pintype "power_in"))
      (node (ref "U1") (pin "G12") (pinfunction "MSEL2_G12") (pintype "input"))
      (node (ref "U1") (pin "G13") (pinfunction "GND_G13") (pintype "power_in"))
      (node (ref "U1") (pin "G4") (pinfunction "GND_G4") (pintype "power_in"))
      (node (ref "U1") (pin "H10") (pinfunction "GND_H10") (pintype "power_in"))
      (node (ref "U1") (pin "H13") (pinfunction "MSEL0_H13") (pintype "input"))
      (node (ref "U1") (pin "H15") (pinfunction "GND_H15") (pintype "power_in"))
      (node (ref "U1") (pin "H16") (pinfunction "GND_H16") (pintype "power_in"))
      (node (ref "U1") (pin "H7") (pinfunction "GND_H7") (pintype "power_in"))
      (node (ref "U1") (pin "H8") (pinfunction "GND_H8") (pintype "power_in"))
      (node (ref "U1") (pin "H9") (pinfunction "GND_H9") (pintype "power_in"))
      (node (ref "U1") (pin "J10") (pinfunction "GND_J10") (pintype "power_in"))
      (node (ref "U1") (pin "J11") (pinfunction "GND_J11") (pintype "power_in"))
      (node (ref "U1") (pin "J7") (pinfunction "GND_J7") (pintype "power_in"))
      (node (ref "U1") (pin "J8") (pinfunction "GND_J8") (pintype "power_in"))
      (node (ref "U1") (pin "J9") (pinfunction "GND_J9") (pintype "power_in"))
      (node (ref "U1") (pin "K12") (pinfunction "GND_K12") (pintype "power_in"))
      (node (ref "U1") (pin "K13") (pinfunction "GND_K13") (pintype "power_in"))
      (node (ref "U1") (pin "K4") (pinfunction "GND_K4") (pintype "power_in"))
      (node (ref "U1") (pin "K6") (pinfunction "GND_K6") (pintype "power_in"))
      (node (ref "U1") (pin "K8") (pinfunction "GND_K8") (pintype "power_in"))
      (node (ref "U1") (pin "L10") (pinfunction "GND_L10") (pintype "power_in"))
      (node (ref "U1") (pin "L11") (pinfunction "GND_L11") (pintype "power_in"))
      (node (ref "U1") (pin "L9") (pinfunction "GND_L9") (pintype "power_in"))
      (node (ref "U1") (pin "M1") (pinfunction "CLK3,_DIFFCLK_1n_M1") (pintype "input"))
      (node (ref "U1") (pin "M12") (pinfunction "GNDA4_M12") (pintype "power_in"))
      (node (ref "U1") (pin "M13") (pinfunction "GND_M13") (pintype "power_in"))
      (node (ref "U1") (pin "M15") (pinfunction "CLK6,_DIFFCLK_3p_M15") (pintype "input"))
      (node (ref "U1") (pin "M16") (pinfunction "CLK7,_DIFFCLK_3n_M16") (pintype "input"))
      (node (ref "U1") (pin "M2") (pinfunction "CLK2,_DIFFCLK_1p_M2") (pintype "input"))
      (node (ref "U1") (pin "M4") (pinfunction "GND_M4") (pintype "power_in"))
      (node (ref "U1") (pin "M5") (pinfunction "GNDA1_M5") (pintype "power_in"))
      (node (ref "U1") (pin "N10") (pinfunction "GND_N10") (pintype "power_in"))
      (node (ref "U1") (pin "N7") (pinfunction "GND_N7") (pintype "power_in"))
      (node (ref "U1") (pin "P12") (pinfunction "GND_P12") (pintype "power_in"))
      (node (ref "U1") (pin "P5") (pinfunction "GND_P5") (pintype "power_in"))
      (node (ref "U1") (pin "R15") (pinfunction "GND_R15") (pintype "power_in"))
      (node (ref "U1") (pin "R2") (pinfunction "GND_R2") (pintype "power_in"))
      (node (ref "U1") (pin "R8") (pinfunction "CLK15,_DIFFCLK_6p_R8") (pintype "input"))
      (node (ref "U1") (pin "R9") (pinfunction "CLK13,_DIFFCLK_7p_R9") (pintype "input"))
      (node (ref "U1") (pin "T9") (pinfunction "CLK12,_DIFFCLK_7n_T9") (pintype "input"))
      (node (ref "U2") (pin "4") (pinfunction "GND_4") (pintype "power_in"))
      (node (ref "U25") (pin "GND") (pinfunction "GND_GND") (pintype "passive"))
    )
    (net (code "156") (name "Net-(U1I-CLK14,_DIFFCLK_6n)") (class "Default")
      (node (ref "U1") (pin "T8") (pinfunction "CLK14,_DIFFCLK_6n_T8") (pintype "input"))
      (node (ref "U25") (pin "OUT") (pinfunction "OUT_OUT") (pintype "passive"))
    )
    (net (code "157") (name "Net-(U1J-TCK)") (class "Default")
      (node (ref "P1") (pin "1") (pinfunction "1_1") (pintype "passive"))
      (node (ref "R4") (pin "1") (pinfunction "1_1") (pintype "passive"))
      (node (ref "U1") (pin "H3") (pinfunction "TCK_H3") (pintype "input"))
    )
    (net (code "158") (name "Net-(U1J-TDI)") (class "Default")
      (node (ref "P1") (pin "9") (pinfunction "9_9") (pintype "passive"))
      (node (ref "R6") (pin "1") (pinfunction "1_1") (pintype "passive"))
      (node (ref "U1") (pin "H4") (pinfunction "TDI_H4") (pintype "input"))
    )
    (net (code "159") (name "Net-(U1J-TDO)") (class "Default")
      (node (ref "P1") (pin "3") (pinfunction "3_3") (pintype "passive"))
      (node (ref "R5") (pin "1") (pinfunction "1_1") (pintype "passive"))
      (node (ref "U1") (pin "J4") (pinfunction "TDO_J4") (pintype "output"))
    )
    (net (code "160") (name "Net-(U1J-TMS)") (class "Default")
      (node (ref "P1") (pin "5") (pinfunction "5_5") (pintype "passive"))
      (node (ref "U1") (pin "J5") (pinfunction "TMS_J5") (pintype "input"))
    )
    (net (code "161") (name "Net-(U1J-nSTATUS)") (class "Default")
      (node (ref "R1") (pin "1") (pinfunction "1_1") (pintype "passive"))
      (node (ref "U1") (pin "F4") (pinfunction "nSTATUS_F4") (pintype "bidirectional"))
    )
    (net (code "162") (name "unconnected-(P1-Pad7)") (class "Default")
      (node (ref "P1") (pin "7") (pinfunction "7_7") (pintype "passive"))
    )
    (net (code "163") (name "unconnected-(P1-Pad8)") (class "Default")
      (node (ref "P1") (pin "8") (pinfunction "8_8") (pintype "passive"))
    )
  )
)
